# Model01.net
KiCad netlist of a schematic drawn in EAGLE
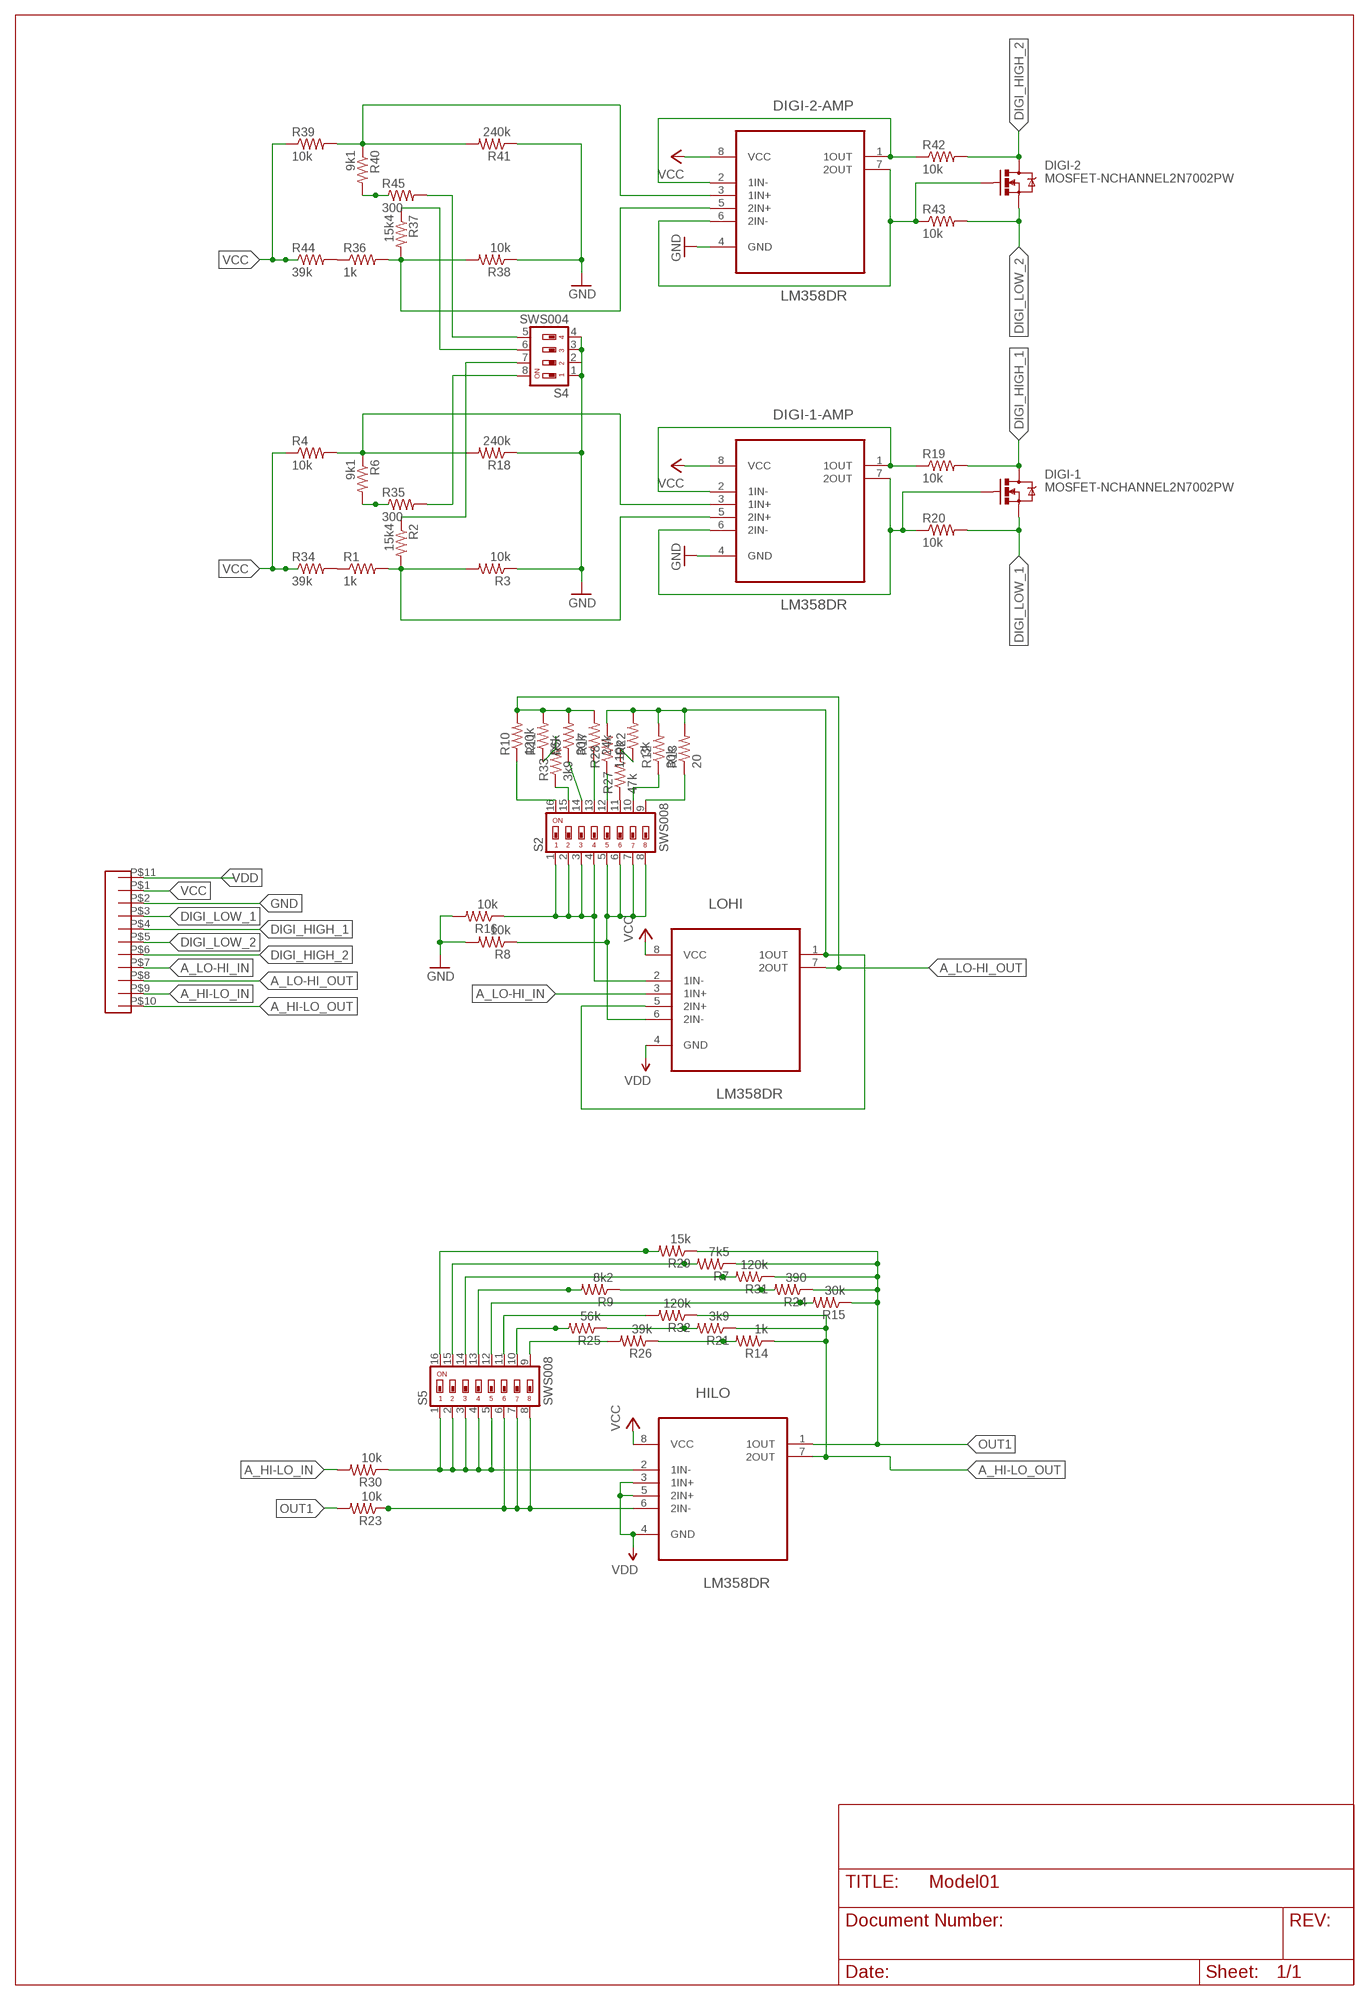
[diagram p0: schematic, sheet 1]

(export (version "E")
  (design (tool "Eeschema 10.0.6"))
  (components
    (comp (ref "DIGI-1")
      (value "MOSFET-NCHANNEL2N7002PW")
      (footprint "eagle-import:SOT323")
      (libsource (lib "eagle-import") (part "MOSFET-NCHANNEL2N7002PW"))
    )
    (comp (ref "DIGI-1-AMP")
      (value "LM358DR")
      (footprint "eagle-import:SOIC127P600X175-8N")
      (libsource (lib "eagle-import") (part "LM358DR"))
    )
    (comp (ref "DIGI-2")
      (value "MOSFET-NCHANNEL2N7002PW")
      (footprint "eagle-import:SOT323")
      (libsource (lib "eagle-import") (part "MOSFET-NCHANNEL2N7002PW"))
    )
    (comp (ref "DIGI-2-AMP")
      (value "LM358DR")
      (footprint "eagle-import:SOIC127P600X175-8N")
      (libsource (lib "eagle-import") (part "LM358DR"))
    )
    (comp (ref "HILO")
      (value "LM358DR")
      (footprint "eagle-import:SOIC127P600X175-8N")
      (libsource (lib "eagle-import") (part "LM358DR"))
    )
    (comp (ref "LOHI")
      (value "LM358DR")
      (footprint "eagle-import:SOIC127P600X175-8N")
      (libsource (lib "eagle-import") (part "LM358DR"))
    )
    (comp (ref "R1")
      (value "1k")
      (footprint "eagle-import:R0805")
      (libsource (lib "eagle-import") (part "R-US_R0805"))
    )
    (comp (ref "R2")
      (value "15k4")
      (footprint "eagle-import:R0805")
      (libsource (lib "eagle-import") (part "R-US_R0805"))
    )
    (comp (ref "R3")
      (value "10k")
      (footprint "eagle-import:R0805")
      (libsource (lib "eagle-import") (part "R-US_R0805"))
    )
    (comp (ref "R4")
      (value "10k")
      (footprint "eagle-import:R0805")
      (libsource (lib "eagle-import") (part "R-US_R0805"))
    )
    (comp (ref "R5")
      (value "30k")
      (footprint "eagle-import:R0805")
      (libsource (lib "eagle-import") (part "R-US_R0805"))
    )
    (comp (ref "R6")
      (value "9k1")
      (footprint "eagle-import:R0805")
      (libsource (lib "eagle-import") (part "R-US_R0805"))
    )
    (comp (ref "R7")
      (value "7k5")
      (footprint "eagle-import:R0805")
      (libsource (lib "eagle-import") (part "R-US_R0805"))
    )
    (comp (ref "R8")
      (value "10k")
      (footprint "eagle-import:R0805")
      (libsource (lib "eagle-import") (part "R-US_R0805"))
    )
    (comp (ref "R9")
      (value "8k2")
      (footprint "eagle-import:R0805")
      (libsource (lib "eagle-import") (part "R-US_R0805"))
    )
    (comp (ref "R10")
      (value "120k")
      (footprint "eagle-import:R0805")
      (libsource (lib "eagle-import") (part "R-US_R0805"))
    )
    (comp (ref "R11")
      (value "56k")
      (footprint "eagle-import:R0805")
      (libsource (lib "eagle-import") (part "R-US_R0805"))
    )
    (comp (ref "R12")
      (value "30k")
      (footprint "eagle-import:R0805")
      (libsource (lib "eagle-import") (part "R-US_R0805"))
    )
    (comp (ref "R13")
      (value "20")
      (footprint "eagle-import:R0805")
      (libsource (lib "eagle-import") (part "R-US_R0805"))
    )
    (comp (ref "R14")
      (value "1k")
      (footprint "eagle-import:R0805")
      (libsource (lib "eagle-import") (part "R-US_R0805"))
    )
    (comp (ref "R15")
      (value "30k")
      (footprint "eagle-import:R0805")
      (libsource (lib "eagle-import") (part "R-US_R0805"))
    )
    (comp (ref "R16")
      (value "10k")
      (footprint "eagle-import:R0805")
      (libsource (lib "eagle-import") (part "R-US_R0805"))
    )
    (comp (ref "R17")
      (value "24k")
      (footprint "eagle-import:R0805")
      (libsource (lib "eagle-import") (part "R-US_R0805"))
    )
    (comp (ref "R18")
      (value "240k")
      (footprint "eagle-import:R0805")
      (libsource (lib "eagle-import") (part "R-US_R0805"))
    )
    (comp (ref "R19")
      (value "10k")
      (footprint "eagle-import:R0805")
      (libsource (lib "eagle-import") (part "R-US_R0805"))
    )
    (comp (ref "R20")
      (value "10k")
      (footprint "eagle-import:R0805")
      (libsource (lib "eagle-import") (part "R-US_R0805"))
    )
    (comp (ref "R21")
      (value "3k9")
      (footprint "eagle-import:R0805")
      (libsource (lib "eagle-import") (part "R-US_R0805"))
    )
    (comp (ref "R22")
      (value "3k")
      (footprint "eagle-import:R0805")
      (libsource (lib "eagle-import") (part "R-US_R0805"))
    )
    (comp (ref "R23")
      (value "10k")
      (footprint "eagle-import:R0805")
      (libsource (lib "eagle-import") (part "R-US_R0805"))
    )
    (comp (ref "R24")
      (value "390")
      (footprint "eagle-import:R0805")
      (libsource (lib "eagle-import") (part "R-US_R0805"))
    )
    (comp (ref "R25")
      (value "56k")
      (footprint "eagle-import:R0805")
      (libsource (lib "eagle-import") (part "R-US_R0805"))
    )
    (comp (ref "R26")
      (value "39k")
      (footprint "eagle-import:R0805")
      (libsource (lib "eagle-import") (part "R-US_R0805"))
    )
    (comp (ref "R27")
      (value "47k")
      (footprint "eagle-import:R0805")
      (libsource (lib "eagle-import") (part "R-US_R0805"))
    )
    (comp (ref "R28")
      (value "110k")
      (footprint "eagle-import:R0805")
      (libsource (lib "eagle-import") (part "R-US_R0805"))
    )
    (comp (ref "R29")
      (value "15k")
      (footprint "eagle-import:R0805")
      (libsource (lib "eagle-import") (part "R-US_R0805"))
    )
    (comp (ref "R30")
      (value "10k")
      (footprint "eagle-import:R0805")
      (libsource (lib "eagle-import") (part "R-US_R0805"))
    )
    (comp (ref "R31")
      (value "120k")
      (footprint "eagle-import:R0805")
      (libsource (lib "eagle-import") (part "R-US_R0805"))
    )
    (comp (ref "R32")
      (value "120k")
      (footprint "eagle-import:R0805")
      (libsource (lib "eagle-import") (part "R-US_R0805"))
    )
    (comp (ref "R33")
      (value "3k9")
      (footprint "eagle-import:R0805")
      (libsource (lib "eagle-import") (part "R-US_R0805"))
    )
    (comp (ref "R34")
      (value "39k")
      (footprint "eagle-import:R0805")
      (libsource (lib "eagle-import") (part "R-US_R0805"))
    )
    (comp (ref "R35")
      (value "300")
      (footprint "eagle-import:R0805")
      (libsource (lib "eagle-import") (part "R-US_R0805"))
    )
    (comp (ref "R36")
      (value "1k")
      (footprint "eagle-import:R0805")
      (libsource (lib "eagle-import") (part "R-US_R0805"))
    )
    (comp (ref "R37")
      (value "15k4")
      (footprint "eagle-import:R0805")
      (libsource (lib "eagle-import") (part "R-US_R0805"))
    )
    (comp (ref "R38")
      (value "10k")
      (footprint "eagle-import:R0805")
      (libsource (lib "eagle-import") (part "R-US_R0805"))
    )
    (comp (ref "R39")
      (value "10k")
      (footprint "eagle-import:R0805")
      (libsource (lib "eagle-import") (part "R-US_R0805"))
    )
    (comp (ref "R40")
      (value "9k1")
      (footprint "eagle-import:R0805")
      (libsource (lib "eagle-import") (part "R-US_R0805"))
    )
    (comp (ref "R41")
      (value "240k")
      (footprint "eagle-import:R0805")
      (libsource (lib "eagle-import") (part "R-US_R0805"))
    )
    (comp (ref "R42")
      (value "10k")
      (footprint "eagle-import:R0805")
      (libsource (lib "eagle-import") (part "R-US_R0805"))
    )
    (comp (ref "R43")
      (value "10k")
      (footprint "eagle-import:R0805")
      (libsource (lib "eagle-import") (part "R-US_R0805"))
    )
    (comp (ref "R44")
      (value "39k")
      (footprint "eagle-import:R0805")
      (libsource (lib "eagle-import") (part "R-US_R0805"))
    )
    (comp (ref "R45")
      (value "300")
      (footprint "eagle-import:R0805")
      (libsource (lib "eagle-import") (part "R-US_R0805"))
    )
    (comp (ref "S2")
      (value "SWS008")
      (footprint "eagle-import:SMS-008")
      (libsource (lib "eagle-import") (part "SWS008"))
    )
    (comp (ref "S4")
      (value "SWS004")
      (footprint "eagle-import:SMS-004")
      (libsource (lib "eagle-import") (part "SWS004"))
    )
    (comp (ref "S5")
      (value "SWS008")
      (footprint "eagle-import:SMS-008")
      (libsource (lib "eagle-import") (part "SWS008"))
    )
    (comp (ref "U$1")
      (value "5.08PITCHTERMINAL")
      (footprint "eagle-import:10KPL508")
      (libsource (lib "eagle-import") (part "5.08PITCHTERMINAL"))
    )
  )
  (nets
    (net (code "1") (name "A_HI-LO_IN") (class "Default")
      (node (ref "R30") (pin "2") (pinfunction "2_2") (pintype "passive"))
      (node (ref "U$1") (pin "P$9") (pinfunction "P$9_P$9") (pintype "bidirectional"))
    )
    (net (code "2") (name "A_HI-LO_OUT") (class "Default")
      (node (ref "HILO") (pin "7") (pinfunction "2OUT_7") (pintype "output"))
      (node (ref "R14") (pin "1") (pinfunction "1_1") (pintype "passive"))
      (node (ref "R21") (pin "1") (pinfunction "1_1") (pintype "passive"))
      (node (ref "R32") (pin "1") (pinfunction "1_1") (pintype "passive"))
      (node (ref "U$1") (pin "P$10") (pinfunction "P$10_P$10") (pintype "bidirectional"))
    )
    (net (code "3") (name "A_LO-HI_IN") (class "Default")
      (node (ref "LOHI") (pin "3") (pinfunction "1IN+_3") (pintype "input"))
      (node (ref "U$1") (pin "P$7") (pinfunction "P$7_P$7") (pintype "bidirectional"))
    )
    (net (code "4") (name "A_LO-HI_OUT") (class "Default")
      (node (ref "LOHI") (pin "7") (pinfunction "2OUT_7") (pintype "output"))
      (node (ref "R10") (pin "2") (pinfunction "2_2") (pintype "passive"))
      (node (ref "R11") (pin "2") (pinfunction "2_2") (pintype "passive"))
      (node (ref "R17") (pin "2") (pinfunction "2_2") (pintype "passive"))
      (node (ref "R5") (pin "2") (pinfunction "2_2") (pintype "passive"))
      (node (ref "U$1") (pin "P$8") (pinfunction "P$8_P$8") (pintype "bidirectional"))
    )
    (net (code "5") (name "DIGI_HIGH_1") (class "Default")
      (node (ref "DIGI-1") (pin "3") (pinfunction "D_3") (pintype "passive"))
      (node (ref "R19") (pin "2") (pinfunction "2_2") (pintype "passive"))
      (node (ref "U$1") (pin "P$4") (pinfunction "P$4_P$4") (pintype "bidirectional"))
    )
    (net (code "6") (name "DIGI_HIGH_2") (class "Default")
      (node (ref "DIGI-2") (pin "3") (pinfunction "D_3") (pintype "passive"))
      (node (ref "R42") (pin "2") (pinfunction "2_2") (pintype "passive"))
      (node (ref "U$1") (pin "P$6") (pinfunction "P$6_P$6") (pintype "bidirectional"))
    )
    (net (code "7") (name "DIGI_LOW_1") (class "Default")
      (node (ref "DIGI-1") (pin "2") (pinfunction "S_2") (pintype "passive"))
      (node (ref "R20") (pin "2") (pinfunction "2_2") (pintype "passive"))
      (node (ref "U$1") (pin "P$3") (pinfunction "P$3_P$3") (pintype "bidirectional"))
    )
    (net (code "8") (name "DIGI_LOW_2") (class "Default")
      (node (ref "DIGI-2") (pin "2") (pinfunction "S_2") (pintype "passive"))
      (node (ref "R43") (pin "2") (pinfunction "2_2") (pintype "passive"))
      (node (ref "U$1") (pin "P$5") (pinfunction "P$5_P$5") (pintype "bidirectional"))
    )
    (net (code "9") (name "GND") (class "Default")
      (node (ref "DIGI-1-AMP") (pin "4") (pinfunction "GND_4") (pintype "passive"))
      (node (ref "DIGI-2-AMP") (pin "4") (pinfunction "GND_4") (pintype "passive"))
      (node (ref "R16") (pin "2") (pinfunction "2_2") (pintype "passive"))
      (node (ref "R18") (pin "1") (pinfunction "1_1") (pintype "passive"))
      (node (ref "R3") (pin "1") (pinfunction "1_1") (pintype "passive"))
      (node (ref "R38") (pin "1") (pinfunction "1_1") (pintype "passive"))
      (node (ref "R41") (pin "1") (pinfunction "1_1") (pintype "passive"))
      (node (ref "R8") (pin "2") (pinfunction "2_2") (pintype "passive"))
      (node (ref "S4") (pin "1") (pinfunction "1_1") (pintype "passive"))
      (node (ref "S4") (pin "2") (pinfunction "2_2") (pintype "passive"))
      (node (ref "S4") (pin "3") (pinfunction "3_3") (pintype "passive"))
      (node (ref "S4") (pin "4") (pinfunction "4_4") (pintype "passive"))
      (node (ref "U$1") (pin "P$2") (pinfunction "P$2_P$2") (pintype "bidirectional"))
    )
    (net (code "10") (name "Net-(DIGI-1-AMP-1IN+)") (class "Default")
      (node (ref "DIGI-1-AMP") (pin "3") (pinfunction "1IN+_3") (pintype "input"))
      (node (ref "R18") (pin "2") (pinfunction "2_2") (pintype "passive"))
      (node (ref "R4") (pin "2") (pinfunction "2_2") (pintype "passive"))
      (node (ref "R6") (pin "1") (pinfunction "1_1") (pintype "passive"))
    )
    (net (code "11") (name "Net-(DIGI-1-AMP-1IN-)") (class "Default")
      (node (ref "DIGI-1-AMP") (pin "1") (pinfunction "1OUT_1") (pintype "output"))
      (node (ref "DIGI-1-AMP") (pin "2") (pinfunction "1IN-_2") (pintype "input"))
      (node (ref "R19") (pin "1") (pinfunction "1_1") (pintype "passive"))
    )
    (net (code "12") (name "Net-(DIGI-1-AMP-2IN+)") (class "Default")
      (node (ref "DIGI-1-AMP") (pin "5") (pinfunction "2IN+_5") (pintype "input"))
      (node (ref "R1") (pin "2") (pinfunction "2_2") (pintype "passive"))
      (node (ref "R2") (pin "2") (pinfunction "2_2") (pintype "passive"))
      (node (ref "R3") (pin "2") (pinfunction "2_2") (pintype "passive"))
    )
    (net (code "13") (name "Net-(DIGI-1-AMP-2IN-)") (class "Default")
      (node (ref "DIGI-1") (pin "1") (pinfunction "G_1") (pintype "passive"))
      (node (ref "DIGI-1-AMP") (pin "6") (pinfunction "2IN-_6") (pintype "input"))
      (node (ref "DIGI-1-AMP") (pin "7") (pinfunction "2OUT_7") (pintype "output"))
      (node (ref "R20") (pin "1") (pinfunction "1_1") (pintype "passive"))
    )
    (net (code "14") (name "Net-(DIGI-2-AMP-1IN+)") (class "Default")
      (node (ref "DIGI-2-AMP") (pin "3") (pinfunction "1IN+_3") (pintype "input"))
      (node (ref "R39") (pin "2") (pinfunction "2_2") (pintype "passive"))
      (node (ref "R40") (pin "1") (pinfunction "1_1") (pintype "passive"))
      (node (ref "R41") (pin "2") (pinfunction "2_2") (pintype "passive"))
    )
    (net (code "15") (name "Net-(DIGI-2-AMP-1IN-)") (class "Default")
      (node (ref "DIGI-2-AMP") (pin "1") (pinfunction "1OUT_1") (pintype "output"))
      (node (ref "DIGI-2-AMP") (pin "2") (pinfunction "1IN-_2") (pintype "input"))
      (node (ref "R42") (pin "1") (pinfunction "1_1") (pintype "passive"))
    )
    (net (code "16") (name "Net-(DIGI-2-AMP-2IN+)") (class "Default")
      (node (ref "DIGI-2-AMP") (pin "5") (pinfunction "2IN+_5") (pintype "input"))
      (node (ref "R36") (pin "2") (pinfunction "2_2") (pintype "passive"))
      (node (ref "R37") (pin "2") (pinfunction "2_2") (pintype "passive"))
      (node (ref "R38") (pin "2") (pinfunction "2_2") (pintype "passive"))
    )
    (net (code "17") (name "Net-(DIGI-2-AMP-2IN-)") (class "Default")
      (node (ref "DIGI-2") (pin "1") (pinfunction "G_1") (pintype "passive"))
      (node (ref "DIGI-2-AMP") (pin "6") (pinfunction "2IN-_6") (pintype "input"))
      (node (ref "DIGI-2-AMP") (pin "7") (pinfunction "2OUT_7") (pintype "output"))
      (node (ref "R43") (pin "1") (pinfunction "1_1") (pintype "passive"))
    )
    (net (code "18") (name "Net-(HILO-1IN-)") (class "Default")
      (node (ref "HILO") (pin "2") (pinfunction "1IN-_2") (pintype "input"))
      (node (ref "R30") (pin "1") (pinfunction "1_1") (pintype "passive"))
      (node (ref "S5") (pin "1") (pinfunction "1_1") (pintype "passive"))
      (node (ref "S5") (pin "2") (pinfunction "2_2") (pintype "passive"))
      (node (ref "S5") (pin "3") (pinfunction "3_3") (pintype "passive"))
      (node (ref "S5") (pin "4") (pinfunction "4_4") (pintype "passive"))
      (node (ref "S5") (pin "5") (pinfunction "5_5") (pintype "passive"))
    )
    (net (code "19") (name "Net-(HILO-2IN-)") (class "Default")
      (node (ref "HILO") (pin "6") (pinfunction "2IN-_6") (pintype "input"))
      (node (ref "R23") (pin "1") (pinfunction "1_1") (pintype "passive"))
      (node (ref "S5") (pin "6") (pinfunction "6_6") (pintype "passive"))
      (node (ref "S5") (pin "7") (pinfunction "7_7") (pintype "passive"))
      (node (ref "S5") (pin "8") (pinfunction "8_8") (pintype "passive"))
    )
    (net (code "20") (name "Net-(LOHI-1IN-)") (class "Default")
      (node (ref "LOHI") (pin "2") (pinfunction "1IN-_2") (pintype "input"))
      (node (ref "R16") (pin "1") (pinfunction "1_1") (pintype "passive"))
      (node (ref "S2") (pin "1") (pinfunction "1_1") (pintype "passive"))
      (node (ref "S2") (pin "2") (pinfunction "2_2") (pintype "passive"))
      (node (ref "S2") (pin "3") (pinfunction "3_3") (pintype "passive"))
      (node (ref "S2") (pin "4") (pinfunction "4_4") (pintype "passive"))
    )
    (net (code "21") (name "Net-(LOHI-1OUT)") (class "Default")
      (node (ref "LOHI") (pin "1") (pinfunction "1OUT_1") (pintype "output"))
      (node (ref "LOHI") (pin "5") (pinfunction "2IN+_5") (pintype "input"))
      (node (ref "R12") (pin "2") (pinfunction "2_2") (pintype "passive"))
      (node (ref "R13") (pin "2") (pinfunction "2_2") (pintype "passive"))
      (node (ref "R22") (pin "2") (pinfunction "2_2") (pintype "passive"))
      (node (ref "R28") (pin "2") (pinfunction "2_2") (pintype "passive"))
    )
    (net (code "22") (name "Net-(LOHI-2IN-)") (class "Default")
      (node (ref "LOHI") (pin "6") (pinfunction "2IN-_6") (pintype "input"))
      (node (ref "R8") (pin "1") (pinfunction "1_1") (pintype "passive"))
      (node (ref "S2") (pin "5") (pinfunction "5_5") (pintype "passive"))
      (node (ref "S2") (pin "6") (pinfunction "6_6") (pintype "passive"))
      (node (ref "S2") (pin "7") (pinfunction "7_7") (pintype "passive"))
      (node (ref "S2") (pin "8") (pinfunction "8_8") (pintype "passive"))
    )
    (net (code "23") (name "Net-(R1-Pad1)") (class "Default")
      (node (ref "R1") (pin "1") (pinfunction "1_1") (pintype "passive"))
      (node (ref "R34") (pin "2") (pinfunction "2_2") (pintype "passive"))
    )
    (net (code "24") (name "Net-(R2-Pad1)") (class "Default")
      (node (ref "R2") (pin "1") (pinfunction "1_1") (pintype "passive"))
      (node (ref "S4") (pin "7") (pinfunction "7_7") (pintype "passive"))
    )
    (net (code "25") (name "Net-(R5-Pad1)") (class "Default")
      (node (ref "R5") (pin "1") (pinfunction "1_1") (pintype "passive"))
      (node (ref "S2") (pin "14") (pinfunction "14_14") (pintype "passive"))
    )
    (net (code "26") (name "Net-(R7-Pad2)") (class "Default")
      (node (ref "R7") (pin "2") (pinfunction "2_2") (pintype "passive"))
      (node (ref "S5") (pin "15") (pinfunction "15_15") (pintype "passive"))
    )
    (net (code "27") (name "Net-(R9-Pad2)") (class "Default")
      (node (ref "R9") (pin "2") (pinfunction "2_2") (pintype "passive"))
      (node (ref "S5") (pin "13") (pinfunction "13_13") (pintype "passive"))
    )
    (net (code "28") (name "Net-(R10-Pad1)") (class "Default")
      (node (ref "R10") (pin "1") (pinfunction "1_1") (pintype "passive"))
      (node (ref "S2") (pin "16") (pinfunction "16_16") (pintype "passive"))
    )
    (net (code "29") (name "Net-(R11-Pad1)") (class "Default")
      (node (ref "R11") (pin "1") (pinfunction "1_1") (pintype "passive"))
      (node (ref "R33") (pin "2") (pinfunction "2_2") (pintype "passive"))
    )
    (net (code "30") (name "Net-(R12-Pad1)") (class "Default")
      (node (ref "R12") (pin "1") (pinfunction "1_1") (pintype "passive"))
      (node (ref "S2") (pin "10") (pinfunction "10_10") (pintype "passive"))
    )
    (net (code "31") (name "Net-(R13-Pad1)") (class "Default")
      (node (ref "R13") (pin "1") (pinfunction "1_1") (pintype "passive"))
      (node (ref "S2") (pin "9") (pinfunction "9_9") (pintype "passive"))
    )
    (net (code "32") (name "Net-(R14-Pad2)") (class "Default")
      (node (ref "R14") (pin "2") (pinfunction "2_2") (pintype "passive"))
      (node (ref "R26") (pin "1") (pinfunction "1_1") (pintype "passive"))
    )
    (net (code "33") (name "Net-(R15-Pad2)") (class "Default")
      (node (ref "R15") (pin "2") (pinfunction "2_2") (pintype "passive"))
      (node (ref "S5") (pin "12") (pinfunction "12_12") (pintype "passive"))
    )
    (net (code "34") (name "Net-(R17-Pad1)") (class "Default")
      (node (ref "R17") (pin "1") (pinfunction "1_1") (pintype "passive"))
      (node (ref "S2") (pin "13") (pinfunction "13_13") (pintype "passive"))
    )
    (net (code "35") (name "Net-(R21-Pad2)") (class "Default")
      (node (ref "R21") (pin "2") (pinfunction "2_2") (pintype "passive"))
      (node (ref "R25") (pin "1") (pinfunction "1_1") (pintype "passive"))
    )
    (net (code "36") (name "Net-(R22-Pad1)") (class "Default")
      (node (ref "R22") (pin "1") (pinfunction "1_1") (pintype "passive"))
      (node (ref "R27") (pin "2") (pinfunction "2_2") (pintype "passive"))
    )
    (net (code "37") (name "Net-(R24-Pad2)") (class "Default")
      (node (ref "R24") (pin "2") (pinfunction "2_2") (pintype "passive"))
      (node (ref "R9") (pin "1") (pinfunction "1_1") (pintype "passive"))
    )
    (net (code "38") (name "Net-(R25-Pad2)") (class "Default")
      (node (ref "R25") (pin "2") (pinfunction "2_2") (pintype "passive"))
      (node (ref "S5") (pin "10") (pinfunction "10_10") (pintype "passive"))
    )
    (net (code "39") (name "Net-(R26-Pad2)") (class "Default")
      (node (ref "R26") (pin "2") (pinfunction "2_2") (pintype "passive"))
      (node (ref "S5") (pin "9") (pinfunction "9_9") (pintype "passive"))
    )
    (net (code "40") (name "Net-(R27-Pad1)") (class "Default")
      (node (ref "R27") (pin "1") (pinfunction "1_1") (pintype "passive"))
      (node (ref "S2") (pin "11") (pinfunction "11_11") (pintype "passive"))
    )
    (net (code "41") (name "Net-(R28-Pad1)") (class "Default")
      (node (ref "R28") (pin "1") (pinfunction "1_1") (pintype "passive"))
      (node (ref "S2") (pin "12") (pinfunction "12_12") (pintype "passive"))
    )
    (net (code "42") (name "Net-(R29-Pad2)") (class "Default")
      (node (ref "R29") (pin "2") (pinfunction "2_2") (pintype "passive"))
      (node (ref "S5") (pin "16") (pinfunction "16_16") (pintype "passive"))
    )
    (net (code "43") (name "Net-(R31-Pad2)") (class "Default")
      (node (ref "R31") (pin "2") (pinfunction "2_2") (pintype "passive"))
      (node (ref "S5") (pin "14") (pinfunction "14_14") (pintype "passive"))
    )
    (net (code "44") (name "Net-(R32-Pad2)") (class "Default")
      (node (ref "R32") (pin "2") (pinfunction "2_2") (pintype "passive"))
      (node (ref "S5") (pin "11") (pinfunction "11_11") (pintype "passive"))
    )
    (net (code "45") (name "Net-(R33-Pad1)") (class "Default")
      (node (ref "R33") (pin "1") (pinfunction "1_1") (pintype "passive"))
      (node (ref "S2") (pin "15") (pinfunction "15_15") (pintype "passive"))
    )
    (net (code "46") (name "Net-(R35-Pad1)") (class "Default")
      (node (ref "R35") (pin "1") (pinfunction "1_1") (pintype "passive"))
      (node (ref "R6") (pin "2") (pinfunction "2_2") (pintype "passive"))
    )
    (net (code "47") (name "Net-(R35-Pad2)") (class "Default")
      (node (ref "R35") (pin "2") (pinfunction "2_2") (pintype "passive"))
      (node (ref "S4") (pin "8") (pinfunction "8_8") (pintype "passive"))
    )
    (net (code "48") (name "Net-(R36-Pad1)") (class "Default")
      (node (ref "R36") (pin "1") (pinfunction "1_1") (pintype "passive"))
      (node (ref "R44") (pin "2") (pinfunction "2_2") (pintype "passive"))
    )
    (net (code "49") (name "Net-(R37-Pad1)") (class "Default")
      (node (ref "R37") (pin "1") (pinfunction "1_1") (pintype "passive"))
      (node (ref "S4") (pin "6") (pinfunction "6_6") (pintype "passive"))
    )
    (net (code "50") (name "Net-(R40-Pad2)") (class "Default")
      (node (ref "R40") (pin "2") (pinfunction "2_2") (pintype "passive"))
      (node (ref "R45") (pin "1") (pinfunction "1_1") (pintype "passive"))
    )
    (net (code "51") (name "Net-(R45-Pad2)") (class "Default")
      (node (ref "R45") (pin "2") (pinfunction "2_2") (pintype "passive"))
      (node (ref "S4") (pin "5") (pinfunction "5_5") (pintype "passive"))
    )
    (net (code "52") (name "OUT1") (class "Default")
      (node (ref "HILO") (pin "1") (pinfunction "1OUT_1") (pintype "output"))
      (node (ref "R15") (pin "1") (pinfunction "1_1") (pintype "passive"))
      (node (ref "R23") (pin "2") (pinfunction "2_2") (pintype "passive"))
      (node (ref "R24") (pin "1") (pinfunction "1_1") (pintype "passive"))
      (node (ref "R29") (pin "1") (pinfunction "1_1") (pintype "passive"))
      (node (ref "R31") (pin "1") (pinfunction "1_1") (pintype "passive"))
      (node (ref "R7") (pin "1") (pinfunction "1_1") (pintype "passive"))
    )
    (net (code "53") (name "VCC") (class "Default")
      (node (ref "DIGI-1-AMP") (pin "8") (pinfunction "VCC_8") (pintype "power_in"))
      (node (ref "DIGI-2-AMP") (pin "8") (pinfunction "VCC_8") (pintype "power_in"))
      (node (ref "HILO") (pin "8") (pinfunction "VCC_8") (pintype "power_in"))
      (node (ref "LOHI") (pin "8") (pinfunction "VCC_8") (pintype "power_in"))
      (node (ref "R34") (pin "1") (pinfunction "1_1") (pintype "passive"))
      (node (ref "R39") (pin "1") (pinfunction "1_1") (pintype "passive"))
      (node (ref "R4") (pin "1") (pinfunction "1_1") (pintype "passive"))
      (node (ref "R44") (pin "1") (pinfunction "1_1") (pintype "passive"))
      (node (ref "U$1") (pin "P$1") (pinfunction "P$1_P$1") (pintype "bidirectional"))
    )
    (net (code "54") (name "VDD") (class "Default")
      (node (ref "HILO") (pin "3") (pinfunction "1IN+_3") (pintype "input"))
      (node (ref "HILO") (pin "4") (pinfunction "GND_4") (pintype "passive"))
      (node (ref "HILO") (pin "5") (pinfunction "2IN+_5") (pintype "input"))
      (node (ref "LOHI") (pin "4") (pinfunction "GND_4") (pintype "passive"))
      (node (ref "U$1") (pin "P$11") (pinfunction "P$11_P$11") (pintype "bidirectional"))
    )
  )
)
